# Sheet1.net
KiCad netlist of a schematic drawn in Altium Designer
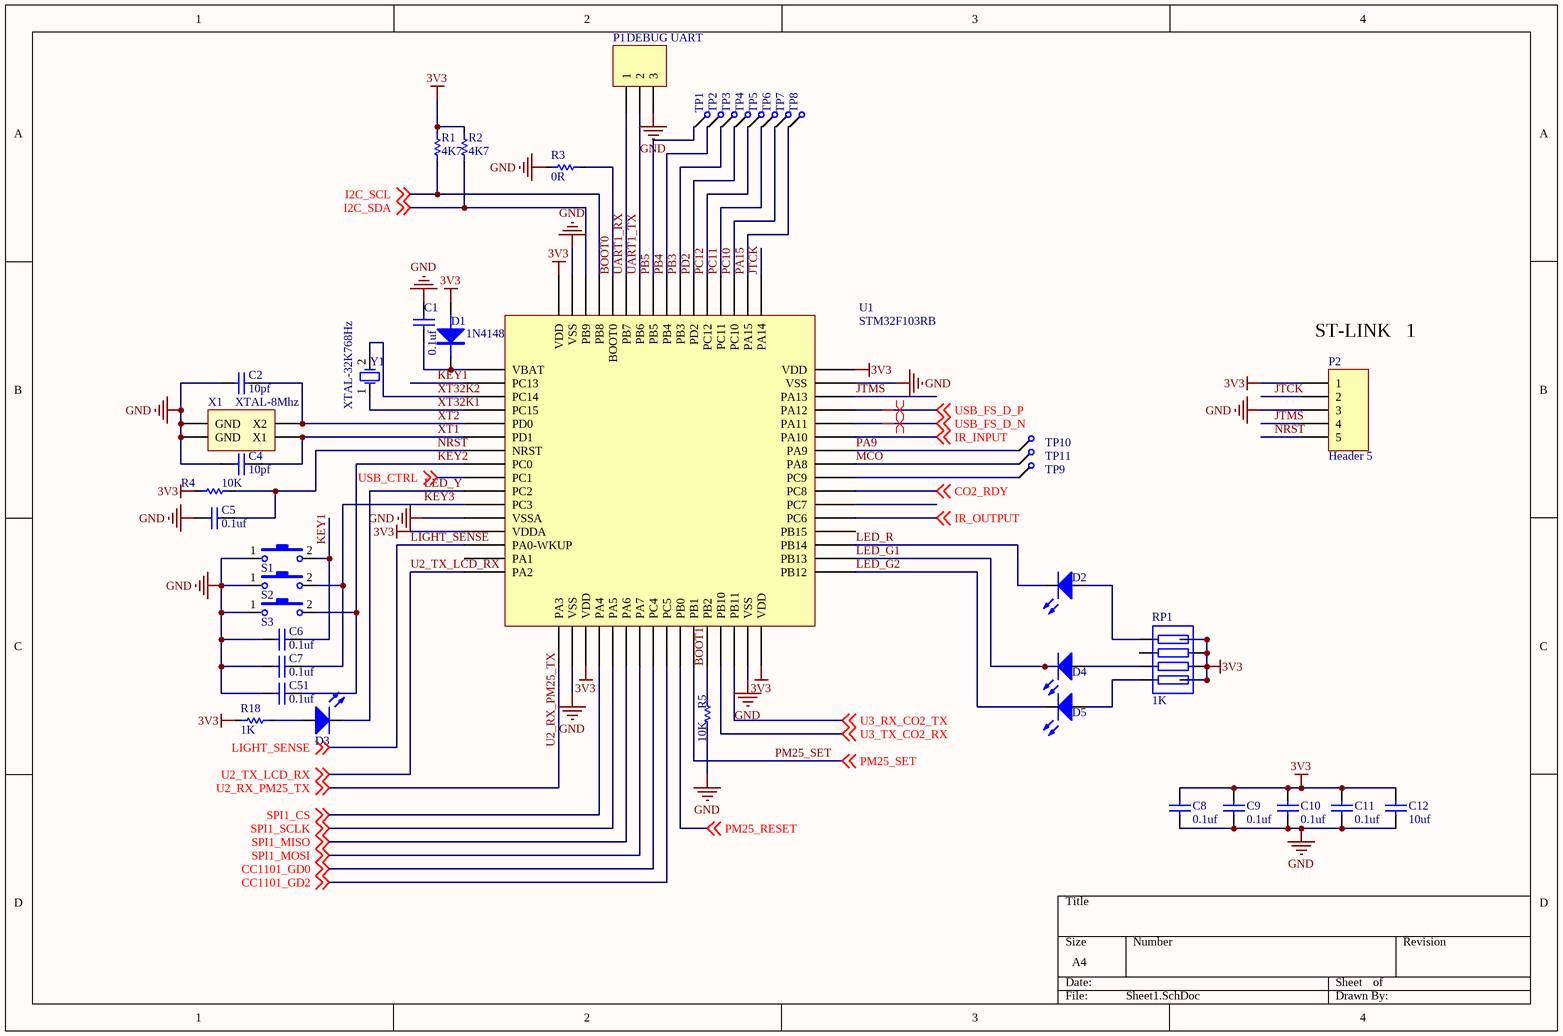
[diagram p0: Sheet1.SchDoc]

(export (version "E")
  (design (tool "Eeschema 10.0.6"))
  (components
    (comp (ref "C1")
      (value "0.1uf")
      (footprint "C0603")
      (description "Capacitor")
      (libsource (lib "liber") (part "Cap"))
    )
    (comp (ref "C2")
      (value "10pf")
      (footprint "C0603")
      (description "Capacitor")
      (fields (field (name "PUBLISHER") "Altium Limited"))
      (libsource (lib "liber") (part "Cap"))
    )
    (comp (ref "C4")
      (value "10pf")
      (footprint "C0603")
      (description "Capacitor")
      (fields (field (name "PUBLISHER") "Altium Limited"))
      (libsource (lib "liber") (part "Cap"))
    )
    (comp (ref "C5")
      (value "0.1uf")
      (footprint "C0603")
      (description "Capacitor")
      (libsource (lib "liber") (part "Cap"))
    )
    (comp (ref "C6")
      (value "0.1uf")
      (footprint "C0603")
      (description "Capacitor")
      (libsource (lib "liber") (part "Cap"))
    )
    (comp (ref "C7")
      (value "0.1uf")
      (footprint "C0603")
      (description "Capacitor")
      (libsource (lib "liber") (part "Cap"))
    )
    (comp (ref "C8")
      (value "0.1uf")
      (footprint "C0603")
      (description "Capacitor")
      (libsource (lib "liber") (part "Cap"))
    )
    (comp (ref "C9")
      (value "0.1uf")
      (footprint "C0603")
      (description "Capacitor")
      (libsource (lib "liber") (part "Cap"))
    )
    (comp (ref "C10")
      (value "0.1uf")
      (footprint "C0603")
      (description "Capacitor")
      (libsource (lib "liber") (part "Cap"))
    )
    (comp (ref "C11")
      (value "0.1uf")
      (footprint "C0603")
      (description "Capacitor")
      (libsource (lib "liber") (part "Cap"))
    )
    (comp (ref "C12")
      (value "10uf")
      (footprint "C1206")
      (description "Capacitor")
      (libsource (lib "liber") (part "Cap"))
    )
    (comp (ref "C51")
      (value "0.1uf")
      (footprint "C0603")
      (description "Capacitor")
      (libsource (lib "liber") (part "Cap"))
    )
    (comp (ref "D1")
      (value "1N4148")
      (footprint "D0805")
      (description "Diode")
      (libsource (lib "liber") (part "DIODE"))
    )
    (comp (ref "D2")
      (value "红色LED")
      (footprint "LED0603")
      (description "Typical INFRARED GaAs LED")
      (fields (field (name "PUBLISHER") "Altium Limited"))
      (libsource (lib "liber") (part "LED"))
    )
    (comp (ref "D3")
      (value "黄色LED")
      (footprint "LED0603")
      (description "Typical INFRARED GaAs LED")
      (fields (field (name "PUBLISHER") "Altium Limited"))
      (libsource (lib "liber") (part "LED"))
    )
    (comp (ref "D4")
      (value "红色LED")
      (footprint "LED0603")
      (description "Typical INFRARED GaAs LED")
      (fields (field (name "PUBLISHER") "Altium Limited"))
      (libsource (lib "liber") (part "LED"))
    )
    (comp (ref "D5")
      (value "红色LED")
      (footprint "LED0603")
      (description "Typical INFRARED GaAs LED")
      (fields (field (name "PUBLISHER") "Altium Limited"))
      (libsource (lib "liber") (part "LED"))
    )
    (comp (ref "P1")
      (value "DEBUG UART")
      (footprint "HDR1X3")
      (description "Header, 3-Pin")
      (fields (field (name "PUBLISHER") "Altium Limited"))
      (libsource (lib "Miscellaneous Connectors") (part "Header 3"))
    )
    (comp (ref "P2")
      (value "Header 5")
      (footprint "HDR1X5")
      (description "Header, 5-Pin")
      (fields (field (name "PUBLISHER") "Altium Limited"))
      (libsource (lib "Miscellaneous Connectors") (part "Header 5"))
    )
    (comp (ref "R1")
      (value "4K7")
      (footprint "R0603")
      (fields (field (name "PUBLISHER") "Altium Limited"))
      (libsource (lib "liber") (part "Res"))
    )
    (comp (ref "R2")
      (value "4K7")
      (footprint "R0603")
      (fields (field (name "PUBLISHER") "Altium Limited"))
      (libsource (lib "liber") (part "Res"))
    )
    (comp (ref "R3")
      (value "0R")
      (footprint "R0603")
      (fields (field (name "PUBLISHER") "Altium Limited"))
      (libsource (lib "liber") (part "Res"))
    )
    (comp (ref "R4")
      (value "10K")
      (footprint "R0603")
      (fields (field (name "PUBLISHER") "Altium Limited"))
      (libsource (lib "liber") (part "Res"))
    )
    (comp (ref "R5")
      (value "10K")
      (footprint "R0603")
      (fields (field (name "PUBLISHER") "Altium Limited"))
      (libsource (lib "liber") (part "Res"))
    )
    (comp (ref "R18")
      (value "1K")
      (footprint "R0603")
      (fields (field (name "PUBLISHER") "Altium Limited"))
      (libsource (lib "liber") (part "Res"))
    )
    (comp (ref "RP1") (value "1K") (footprint "R_PACK4_SMD") (libsource (lib "liber") (part "RESPACK4")))
    (comp (ref "S1")
      (value "SW-PB")
      (footprint "SWPB_SMD_90D_48_18_15")
      (description "Switch")
      (fields (field (name "PUBLISHER") "Altium Limited"))
      (libsource (lib "liber") (part "SW-PB"))
    )
    (comp (ref "S2")
      (value "SW-PB")
      (footprint "SWPB_SMD_90D_48_18_15")
      (description "Switch")
      (fields (field (name "PUBLISHER") "Altium Limited"))
      (libsource (lib "liber") (part "SW-PB"))
    )
    (comp (ref "S3")
      (value "SW-PB")
      (footprint "liber:SW2*1Small")
      (description "Switch")
      (fields (field (name "PUBLISHER") "Altium Limited"))
      (libsource (lib "liber") (part "SW-PB"))
    )
    (comp (ref "TP1")
      (value "TestPoint")
      (footprint "TP_0.8")
      (description "一个测试点")
      (libsource (lib "liber") (part "TestPoint"))
    )
    (comp (ref "TP2")
      (value "TestPoint")
      (footprint "TP_0.8")
      (description "一个测试点")
      (libsource (lib "liber") (part "TestPoint"))
    )
    (comp (ref "TP3")
      (value "TestPoint")
      (footprint "TP_0.8")
      (description "一个测试点")
      (libsource (lib "liber") (part "TestPoint"))
    )
    (comp (ref "TP4")
      (value "TestPoint")
      (footprint "TP_0.8")
      (description "一个测试点")
      (libsource (lib "liber") (part "TestPoint"))
    )
    (comp (ref "TP5")
      (value "TestPoint")
      (footprint "TP_0.8")
      (description "一个测试点")
      (libsource (lib "liber") (part "TestPoint"))
    )
    (comp (ref "TP6")
      (value "TestPoint")
      (footprint "TP_0.8")
      (description "一个测试点")
      (libsource (lib "liber") (part "TestPoint"))
    )
    (comp (ref "TP7")
      (value "TestPoint")
      (footprint "TP_0.8")
      (description "一个测试点")
      (libsource (lib "liber") (part "TestPoint"))
    )
    (comp (ref "TP8")
      (value "TestPoint")
      (footprint "TP_0.8")
      (description "一个测试点")
      (libsource (lib "liber") (part "TestPoint"))
    )
    (comp (ref "TP9")
      (value "TestPoint")
      (footprint "TP_0.8")
      (description "一个测试点")
      (libsource (lib "liber") (part "TestPoint"))
    )
    (comp (ref "TP10")
      (value "TestPoint")
      (footprint "TP_0.8")
      (description "一个测试点")
      (libsource (lib "liber") (part "TestPoint"))
    )
    (comp (ref "TP11")
      (value "TestPoint")
      (footprint "TP_0.8")
      (description "一个测试点")
      (libsource (lib "liber") (part "TestPoint"))
    )
    (comp (ref "U1")
      (value "STM32F103RB")
      (footprint "STM32F103RB")
      (libsource (lib "liber") (part "STM32F103RB"))
    )
    (comp (ref "X1") (value "XTAL-8Mhz") (footprint "XTAL5032") (libsource (lib "liber") (part "XTALSMT")))
    (comp (ref "Y1")
      (value "XTAL-32K768Hz")
      (footprint "CRY_S")
      (description "Crystal Oscillator 32K")
      (fields (field (name "PUBLISHER") "Altium Limited"))
      (libsource (lib "liber") (part "XTAL"))
    )
  )
  (nets
    (net (code "1") (name "/BOOT0") (class "Default")
      (node (ref "R3") (pin "2") (pinfunction "2_2") (pintype "passive"))
      (node (ref "U1") (pin "60") (pinfunction "BOOT0_60") (pintype "passive"))
    )
    (net (code "2") (name "/BOOT1") (class "Default")
      (node (ref "R5") (pin "2") (pinfunction "2_2") (pintype "passive"))
      (node (ref "U1") (pin "28") (pinfunction "PB2_28") (pintype "passive"))
    )
    (net (code "3") (name "/JTCK") (class "Default")
      (node (ref "P2") (pin "2") (pinfunction "2_2") (pintype "passive"))
      (node (ref "U1") (pin "49") (pinfunction "PA14_49") (pintype "passive"))
    )
    (net (code "4") (name "/JTMS") (class "Default")
      (node (ref "P2") (pin "4") (pinfunction "4_4") (pintype "passive"))
      (node (ref "U1") (pin "46") (pinfunction "PA13_46") (pintype "passive"))
    )
    (net (code "5") (name "/KEY1") (class "Default")
      (node (ref "C6") (pin "1") (pinfunction "1_1") (pintype "passive"))
      (node (ref "S1") (pin "2") (pinfunction "2_2") (pintype "passive"))
      (node (ref "U1") (pin "2") (pinfunction "PC13_2") (pintype "passive"))
    )
    (net (code "6") (name "/KEY2") (class "Default")
      (node (ref "C51") (pin "2") (pinfunction "2_2") (pintype "passive"))
      (node (ref "S3") (pin "2") (pinfunction "2_2") (pintype "passive"))
      (node (ref "U1") (pin "8") (pinfunction "PC0_8") (pintype "passive"))
    )
    (net (code "7") (name "/KEY3") (class "Default")
      (node (ref "C7") (pin "1") (pinfunction "1_1") (pintype "passive"))
      (node (ref "S2") (pin "2") (pinfunction "2_2") (pintype "passive"))
      (node (ref "U1") (pin "11") (pinfunction "PC3_11") (pintype "passive"))
    )
    (net (code "8") (name "/LED_G1") (class "Default")
      (node (ref "D4") (pin "2") (pinfunction "K_2") (pintype "passive"))
      (node (ref "U1") (pin "34") (pinfunction "PB13_34") (pintype "passive"))
    )
    (net (code "9") (name "/LED_G2") (class "Default")
      (node (ref "D5") (pin "2") (pinfunction "K_2") (pintype "passive"))
      (node (ref "U1") (pin "33") (pinfunction "PB12_33") (pintype "passive"))
    )
    (net (code "10") (name "/LED_R") (class "Default")
      (node (ref "D2") (pin "2") (pinfunction "K_2") (pintype "passive"))
      (node (ref "U1") (pin "35") (pinfunction "PB14_35") (pintype "passive"))
    )
    (net (code "11") (name "/LED_Y") (class "Default")
      (node (ref "D3") (pin "2") (pinfunction "K_2") (pintype "passive"))
      (node (ref "U1") (pin "10") (pinfunction "PC2_10") (pintype "passive"))
    )
    (net (code "12") (name "/MCO") (class "Default")
      (node (ref "TP11") (pin "1") (pinfunction "1_1") (pintype "passive"))
      (node (ref "U1") (pin "41") (pinfunction "PA8_41") (pintype "passive"))
    )
    (net (code "13") (name "/NRST") (class "Default")
      (node (ref "C5") (pin "1") (pinfunction "1_1") (pintype "passive"))
      (node (ref "P2") (pin "5") (pinfunction "5_5") (pintype "passive"))
      (node (ref "R4") (pin "1") (pinfunction "1_1") (pintype "passive"))
      (node (ref "U1") (pin "7") (pinfunction "NRST_7") (pintype "passive"))
    )
    (net (code "14") (name "/PA9") (class "Default")
      (node (ref "TP10") (pin "1") (pinfunction "1_1") (pintype "passive"))
      (node (ref "U1") (pin "42") (pinfunction "PA9_42") (pintype "passive"))
    )
    (net (code "15") (name "/PA15") (class "Default")
      (node (ref "TP8") (pin "1") (pinfunction "1_1") (pintype "passive"))
      (node (ref "U1") (pin "50") (pinfunction "PA15_50") (pintype "passive"))
    )
    (net (code "16") (name "/PB3") (class "Default")
      (node (ref "TP3") (pin "1") (pinfunction "1_1") (pintype "passive"))
      (node (ref "U1") (pin "55") (pinfunction "PB3_55") (pintype "passive"))
    )
    (net (code "17") (name "/PB4") (class "Default")
      (node (ref "TP2") (pin "1") (pinfunction "1_1") (pintype "passive"))
      (node (ref "U1") (pin "56") (pinfunction "PB4_56") (pintype "passive"))
    )
    (net (code "18") (name "/PB5") (class "Default")
      (node (ref "TP1") (pin "1") (pinfunction "1_1") (pintype "passive"))
      (node (ref "U1") (pin "57") (pinfunction "PB5_57") (pintype "passive"))
    )
    (net (code "19") (name "/PC10") (class "Default")
      (node (ref "TP7") (pin "1") (pinfunction "1_1") (pintype "passive"))
      (node (ref "U1") (pin "51") (pinfunction "PC10_51") (pintype "passive"))
    )
    (net (code "20") (name "/PC11") (class "Default")
      (node (ref "TP6") (pin "1") (pinfunction "1_1") (pintype "passive"))
      (node (ref "U1") (pin "52") (pinfunction "PC11_52") (pintype "passive"))
    )
    (net (code "21") (name "/PC12") (class "Default")
      (node (ref "TP5") (pin "1") (pinfunction "1_1") (pintype "passive"))
      (node (ref "U1") (pin "53") (pinfunction "PC12_53") (pintype "passive"))
    )
    (net (code "22") (name "/PD2") (class "Default")
      (node (ref "TP4") (pin "1") (pinfunction "1_1") (pintype "passive"))
      (node (ref "U1") (pin "54") (pinfunction "PD2_54") (pintype "passive"))
    )
    (net (code "23") (name "/UART1_RX") (class "Default")
      (node (ref "P1") (pin "1") (pinfunction "1_1") (pintype "passive"))
      (node (ref "U1") (pin "59") (pinfunction "PB7_59") (pintype "passive"))
    )
    (net (code "24") (name "/UART1_TX") (class "Default")
      (node (ref "P1") (pin "2") (pinfunction "2_2") (pintype "passive"))
      (node (ref "U1") (pin "58") (pinfunction "PB6_58") (pintype "passive"))
    )
    (net (code "25") (name "/XT1") (class "Default")
      (node (ref "C4") (pin "1") (pinfunction "1_1") (pintype "passive"))
      (node (ref "U1") (pin "6") (pinfunction "PD1_6") (pintype "passive"))
      (node (ref "X1") (pin "1") (pinfunction "X1_1") (pintype "passive"))
    )
    (net (code "26") (name "/XT2") (class "Default")
      (node (ref "C2") (pin "2") (pinfunction "2_2") (pintype "passive"))
      (node (ref "U1") (pin "5") (pinfunction "PD0_5") (pintype "passive"))
      (node (ref "X1") (pin "3") (pinfunction "X2_3") (pintype "passive"))
    )
    (net (code "27") (name "/XT32K1") (class "Default")
      (node (ref "U1") (pin "4") (pinfunction "PC15_4") (pintype "passive"))
      (node (ref "Y1") (pin "1") (pinfunction "OSC1_1") (pintype "passive"))
    )
    (net (code "28") (name "/XT32K2") (class "Default")
      (node (ref "U1") (pin "3") (pinfunction "PC14_3") (pintype "passive"))
      (node (ref "Y1") (pin "2") (pinfunction "OSC2_2") (pintype "passive"))
    )
    (net (code "29") (name "3V3") (class "Default")
      (node (ref "C10") (pin "2") (pinfunction "2_2") (pintype "passive"))
      (node (ref "C11") (pin "2") (pinfunction "2_2") (pintype "passive"))
      (node (ref "C12") (pin "2") (pinfunction "2_2") (pintype "passive"))
      (node (ref "C8") (pin "2") (pinfunction "2_2") (pintype "passive"))
      (node (ref "C9") (pin "2") (pinfunction "2_2") (pintype "passive"))
      (node (ref "D1") (pin "1") (pinfunction "A_1") (pintype "passive"))
      (node (ref "P2") (pin "1") (pinfunction "1_1") (pintype "passive"))
      (node (ref "R1") (pin "2") (pinfunction "2_2") (pintype "passive"))
      (node (ref "R18") (pin "1") (pinfunction "1_1") (pintype "passive"))
      (node (ref "R2") (pin "2") (pinfunction "2_2") (pintype "passive"))
      (node (ref "R4") (pin "2") (pinfunction "2_2") (pintype "passive"))
      (node (ref "RP1") (pin "1") (pintype "passive"))
      (node (ref "RP1") (pin "3") (pintype "passive"))
      (node (ref "RP1") (pin "5") (pintype "passive"))
      (node (ref "RP1") (pin "7") (pintype "passive"))
      (node (ref "U1") (pin "13") (pinfunction "VDDA_13") (pintype "passive"))
      (node (ref "U1") (pin "19") (pinfunction "VDD_19") (pintype "passive"))
      (node (ref "U1") (pin "32") (pinfunction "VDD_32") (pintype "passive"))
      (node (ref "U1") (pin "48") (pinfunction "VDD_48") (pintype "passive"))
      (node (ref "U1") (pin "64") (pinfunction "VDD_64") (pintype "passive"))
    )
    (net (code "30") (name "CC1101_GD0") (class "Default")
      (node (ref "U1") (pin "24") (pinfunction "PC4_24") (pintype "passive"))
    )
    (net (code "31") (name "CC1101_GD2") (class "Default")
      (node (ref "U1") (pin "25") (pinfunction "PC5_25") (pintype "passive"))
    )
    (net (code "32") (name "CO2_RDY") (class "Default")
      (node (ref "U1") (pin "39") (pinfunction "PC8_39") (pintype "passive"))
    )
    (net (code "33") (name "GND") (class "Default")
      (node (ref "C1") (pin "2") (pinfunction "2_2") (pintype "passive"))
      (node (ref "C10") (pin "1") (pinfunction "1_1") (pintype "passive"))
      (node (ref "C11") (pin "1") (pinfunction "1_1") (pintype "passive"))
      (node (ref "C12") (pin "1") (pinfunction "1_1") (pintype "passive"))
      (node (ref "C2") (pin "1") (pinfunction "1_1") (pintype "passive"))
      (node (ref "C4") (pin "2") (pinfunction "2_2") (pintype "passive"))
      (node (ref "C5") (pin "2") (pinfunction "2_2") (pintype "passive"))
      (node (ref "C51") (pin "1") (pinfunction "1_1") (pintype "passive"))
      (node (ref "C6") (pin "2") (pinfunction "2_2") (pintype "passive"))
      (node (ref "C7") (pin "2") (pinfunction "2_2") (pintype "passive"))
      (node (ref "C8") (pin "1") (pinfunction "1_1") (pintype "passive"))
      (node (ref "C9") (pin "1") (pinfunction "1_1") (pintype "passive"))
      (node (ref "P1") (pin "3") (pinfunction "3_3") (pintype "passive"))
      (node (ref "P2") (pin "3") (pinfunction "3_3") (pintype "passive"))
      (node (ref "R3") (pin "1") (pinfunction "1_1") (pintype "passive"))
      (node (ref "R5") (pin "1") (pinfunction "1_1") (pintype "passive"))
      (node (ref "S1") (pin "1") (pinfunction "1_1") (pintype "passive"))
      (node (ref "S2") (pin "1") (pinfunction "1_1") (pintype "passive"))
      (node (ref "S3") (pin "1") (pinfunction "1_1") (pintype "passive"))
      (node (ref "U1") (pin "12") (pinfunction "VSSA_12") (pintype "passive"))
      (node (ref "U1") (pin "18") (pinfunction "VSS_18") (pintype "passive"))
      (node (ref "U1") (pin "31") (pinfunction "VSS_31") (pintype "passive"))
      (node (ref "U1") (pin "47") (pinfunction "VSS_47") (pintype "passive"))
      (node (ref "U1") (pin "63") (pinfunction "VSS_63") (pintype "passive"))
      (node (ref "X1") (pin "2") (pinfunction "GND_2") (pintype "passive"))
      (node (ref "X1") (pin "4") (pinfunction "GND_4") (pintype "passive"))
    )
    (net (code "34") (name "I2C_SCL") (class "Default")
      (node (ref "R1") (pin "1") (pinfunction "1_1") (pintype "passive"))
      (node (ref "U1") (pin "61") (pinfunction "PB8_61") (pintype "passive"))
    )
    (net (code "35") (name "I2C_SDA") (class "Default")
      (node (ref "R2") (pin "1") (pinfunction "1_1") (pintype "passive"))
      (node (ref "U1") (pin "62") (pinfunction "PB9_62") (pintype "passive"))
    )
    (net (code "36") (name "IR_INPUT") (class "Default")
      (node (ref "U1") (pin "43") (pinfunction "PA10_43") (pintype "passive"))
    )
    (net (code "37") (name "IR_OUTPUT") (class "Default")
      (node (ref "U1") (pin "37") (pinfunction "PC6_37") (pintype "passive"))
    )
    (net (code "38") (name "LIGHT_SENSE") (class "Default")
      (node (ref "U1") (pin "14") (pinfunction "PA0-WKUP_14") (pintype "passive"))
    )
    (net (code "39") (name "Net-(D1-K)") (class "Default")
      (node (ref "C1") (pin "1") (pinfunction "1_1") (pintype "passive"))
      (node (ref "D1") (pin "2") (pinfunction "K_2") (pintype "passive"))
      (node (ref "U1") (pin "1") (pinfunction "VBAT_1") (pintype "passive"))
    )
    (net (code "40") (name "Net-(D2-A)") (class "Default")
      (node (ref "D2") (pin "1") (pinfunction "A_1") (pintype "passive"))
      (node (ref "RP1") (pin "8") (pintype "passive"))
    )
    (net (code "41") (name "Net-(D3-A)") (class "Default")
      (node (ref "D3") (pin "1") (pinfunction "A_1") (pintype "passive"))
      (node (ref "R18") (pin "2") (pinfunction "2_2") (pintype "passive"))
    )
    (net (code "42") (name "Net-(D4-A)") (class "Default")
      (node (ref "D4") (pin "1") (pinfunction "A_1") (pintype "passive"))
      (node (ref "RP1") (pin "4") (pintype "passive"))
    )
    (net (code "43") (name "Net-(D5-A)") (class "Default")
      (node (ref "D5") (pin "1") (pinfunction "A_1") (pintype "passive"))
      (node (ref "RP1") (pin "2") (pintype "passive"))
    )
    (net (code "44") (name "Net-(U1-PC9)") (class "Default")
      (node (ref "TP9") (pin "1") (pinfunction "1_1") (pintype "passive"))
      (node (ref "U1") (pin "40") (pinfunction "PC9_40") (pintype "passive"))
    )
    (net (code "45") (name "PM25_RESET") (class "Default")
      (node (ref "U1") (pin "26") (pinfunction "PB0_26") (pintype "passive"))
    )
    (net (code "46") (name "PM25_SET") (class "Default")
      (node (ref "U1") (pin "27") (pinfunction "PB1_27") (pintype "passive"))
    )
    (net (code "47") (name "SPI1_CS") (class "Default")
      (node (ref "U1") (pin "20") (pinfunction "PA4_20") (pintype "passive"))
    )
    (net (code "48") (name "SPI1_MISO") (class "Default")
      (node (ref "U1") (pin "22") (pinfunction "PA6_22") (pintype "passive"))
    )
    (net (code "49") (name "SPI1_MOSI") (class "Default")
      (node (ref "U1") (pin "23") (pinfunction "PA7_23") (pintype "passive"))
    )
    (net (code "50") (name "SPI1_SCLK") (class "Default")
      (node (ref "U1") (pin "21") (pinfunction "PA5_21") (pintype "passive"))
    )
    (net (code "51") (name "U2_RX_PM25_TX") (class "Default")
      (node (ref "U1") (pin "17") (pinfunction "PA3_17") (pintype "passive"))
    )
    (net (code "52") (name "U2_TX_LCD_RX") (class "Default")
      (node (ref "U1") (pin "16") (pinfunction "PA2_16") (pintype "passive"))
    )
    (net (code "53") (name "U3_RX_CO2_TX") (class "Default")
      (node (ref "U1") (pin "30") (pinfunction "PB11_30") (pintype "passive"))
    )
    (net (code "54") (name "U3_TX_CO2_RX") (class "Default")
      (node (ref "U1") (pin "29") (pinfunction "PB10_29") (pintype "passive"))
    )
    (net (code "55") (name "USB_CTRL") (class "Default")
      (node (ref "U1") (pin "9") (pinfunction "PC1_9") (pintype "passive"))
    )
    (net (code "56") (name "USB_FS_D_N") (class "Default")
      (node (ref "U1") (pin "44") (pinfunction "PA11_44") (pintype "passive"))
    )
    (net (code "57") (name "USB_FS_D_P") (class "Default")
      (node (ref "U1") (pin "45") (pinfunction "PA12_45") (pintype "passive"))
    )
    (net (code "58") (name "unconnected-(RP1-Pad6)") (class "Default")
      (node (ref "RP1") (pin "6") (pintype "passive"))
    )
    (net (code "59") (name "unconnected-(U1-PA1-Pad15)") (class "Default")
      (node (ref "U1") (pin "15") (pinfunction "PA1_15") (pintype "passive"))
    )
    (net (code "60") (name "unconnected-(U1-PB15-Pad36)") (class "Default")
      (node (ref "U1") (pin "36") (pinfunction "PB15_36") (pintype "passive"))
    )
    (net (code "61") (name "unconnected-(U1-PC7-Pad38)") (class "Default")
      (node (ref "U1") (pin "38") (pinfunction "PC7_38") (pintype "passive"))
    )
  )
)
